# GPSPLLOCXO.net
KiCad netlist of a schematic drawn in EAGLE
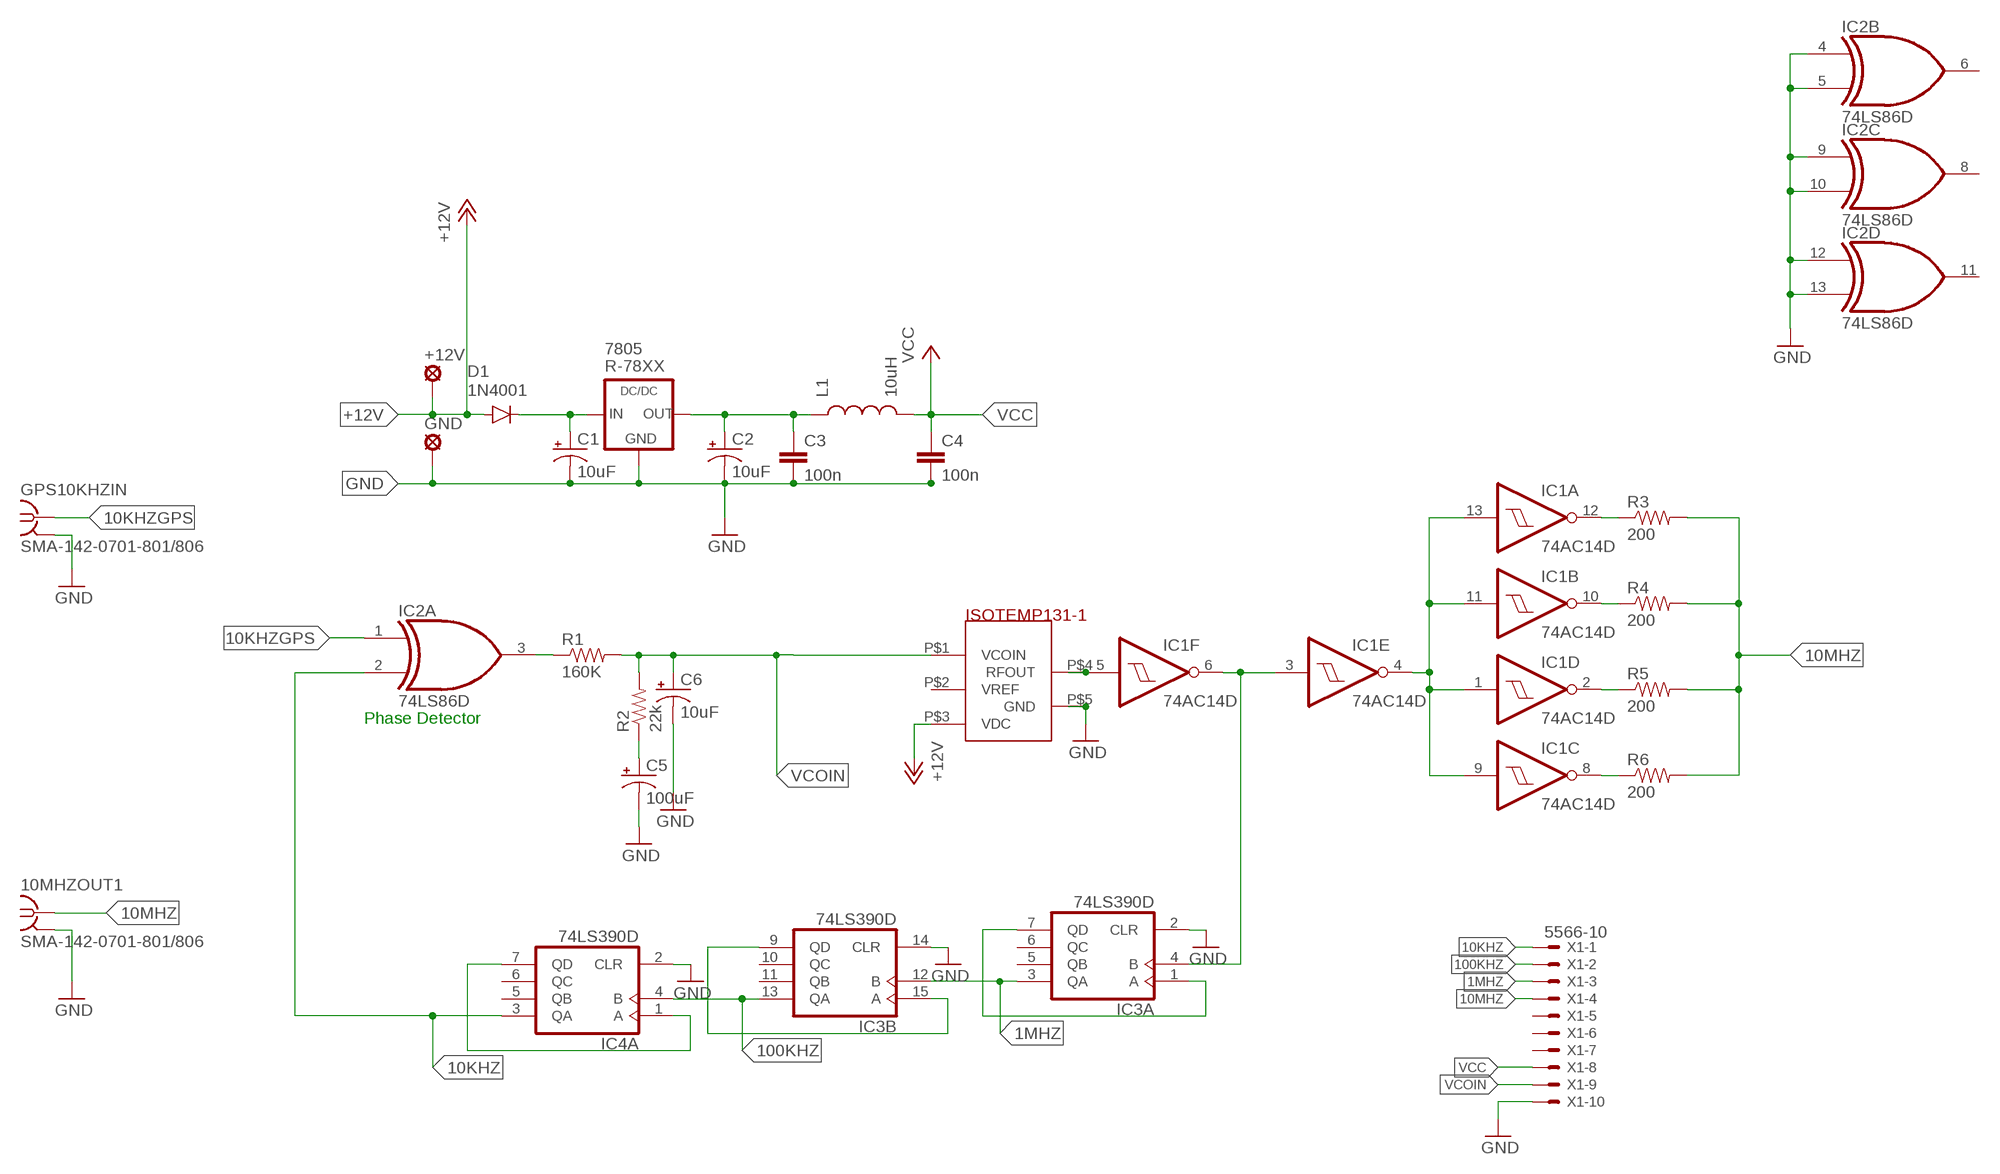
[diagram p0: schematic, sheet 1]

(export (version "E")
  (design (tool "Eeschema 10.0.6"))
  (components
    (comp (ref "+12V")
      (value "LSP13")
      (footprint "eagle-import:LSP13")
      (libsource (lib "eagle-import") (part "LSP13"))
    )
    (comp (ref "10MHZOUT1")
      (value "SMA-142-0701-801/806")
      (footprint "eagle-import:J502-ND-142-0701-801_806")
      (fields (field (name "MF") "JOHNSON COMPONENTS") (field (name "MPN") "142-0701-801"))
      (libsource (lib "eagle-import") (part "SMA-142-0701-801/806"))
    )
    (comp (ref "7805")
      (value "R-78XX")
      (footprint "eagle-import:R-78XX")
      (libsource (lib "eagle-import") (part "R-78XX"))
    )
    (comp (ref "C1")
      (value "10uF")
      (footprint "eagle-import:EIA3216")
      (libsource (lib "eagle-import") (part "10UF-16V-10%(TANT)"))
    )
    (comp (ref "C2")
      (value "10uF")
      (footprint "eagle-import:EIA3216")
      (libsource (lib "eagle-import") (part "10UF-16V-10%(TANT)"))
    )
    (comp (ref "C3")
      (value "100n")
      (footprint "eagle-import:0805")
      (libsource (lib "eagle-import") (part "1.0UF-25V-+80/-20(0805)"))
    )
    (comp (ref "C4")
      (value "100n")
      (footprint "eagle-import:0805")
      (libsource (lib "eagle-import") (part "1.0UF-25V-+80/-20(0805)"))
    )
    (comp (ref "C5")
      (value "100uF")
      (footprint "eagle-import:EIA7343")
      (libsource (lib "eagle-import") (part "100UF-10V-10%(TANT)"))
    )
    (comp (ref "C6")
      (value "10uF")
      (footprint "eagle-import:EIA3216")
      (libsource (lib "eagle-import") (part "10UF-16V-10%(TANT)"))
    )
    (comp (ref "D1")
      (value "1N4001")
      (footprint "eagle-import:SMA-DIODE")
      (libsource (lib "eagle-import") (part "DIODESMA"))
    )
    (comp (ref "GND")
      (value "LSP13")
      (footprint "eagle-import:LSP13")
      (libsource (lib "eagle-import") (part "LSP13"))
    )
    (comp (ref "GPS10KHZIN")
      (value "SMA-142-0701-801/806")
      (footprint "eagle-import:J502-ND-142-0701-801_806")
      (fields (field (name "MF") "JOHNSON COMPONENTS") (field (name "MPN") "142-0701-801"))
      (libsource (lib "eagle-import") (part "SMA-142-0701-801/806"))
    )
    (comp (ref "IC1")
      (value "74AC14D")
      (footprint "eagle-import:SO14")
      (libsource (lib "eagle-import") (part "7414DAC"))
    )
    (comp (ref "IC2")
      (value "74LS86D")
      (footprint "eagle-import:SO14")
      (libsource (lib "eagle-import") (part "7486DLS"))
    )
    (comp (ref "IC3")
      (value "74LS390D")
      (footprint "eagle-import:SO16")
      (libsource (lib "eagle-import") (part "74390DLS"))
    )
    (comp (ref "IC4")
      (value "74LS390D")
      (footprint "eagle-import:SO16")
      (libsource (lib "eagle-import") (part "74390DLS"))
    )
    (comp (ref "ISOTEMP131-1")
      (value "ISOTEMP-131-191")
      (footprint "eagle-import:131")
      (libsource (lib "eagle-import") (part "ISOTEMP-131-191"))
    )
    (comp (ref "L1")
      (value "10uH")
      (footprint "eagle-import:1210")
      (libsource (lib "eagle-import") (part "INDUCTOR1210"))
    )
    (comp (ref "R1")
      (value "160K")
      (footprint "eagle-import:0805")
      (libsource (lib "eagle-import") (part "RESISTOR0805-RES"))
    )
    (comp (ref "R2")
      (value "22k")
      (footprint "eagle-import:0805")
      (libsource (lib "eagle-import") (part "RESISTOR0805-RES"))
    )
    (comp (ref "R3")
      (value "200")
      (footprint "eagle-import:0805")
      (libsource (lib "eagle-import") (part "RESISTOR0805-RES"))
    )
    (comp (ref "R4")
      (value "200")
      (footprint "eagle-import:0805")
      (libsource (lib "eagle-import") (part "RESISTOR0805-RES"))
    )
    (comp (ref "R5")
      (value "200")
      (footprint "eagle-import:0805")
      (libsource (lib "eagle-import") (part "RESISTOR0805-RES"))
    )
    (comp (ref "R6")
      (value "200")
      (footprint "eagle-import:0805")
      (libsource (lib "eagle-import") (part "RESISTOR0805-RES"))
    )
    (comp (ref "X1")
      (value "5566-10")
      (footprint "eagle-import:5566-10")
      (libsource (lib "eagle-import") (part "5566-10"))
    )
  )
  (nets
    (net (code "1") (name "+12V") (class "Default")
      (node (ref "+12V") (pin "MP") (pinfunction "MP_MP") (pintype "passive"))
      (node (ref "D1") (pin "A") (pinfunction "A_A") (pintype "passive"))
      (node (ref "ISOTEMP131-1") (pin "P$3") (pinfunction "VDC_P$3") (pintype "power_in"))
    )
    (net (code "2") (name "1MHZ") (class "Default")
      (node (ref "IC3") (pin "12") (pinfunction "B_12") (pintype "input"))
      (node (ref "IC3") (pin "3") (pinfunction "QA_3") (pintype "output"))
      (node (ref "X1") (pin "3") (pinfunction "S_3") (pintype "passive"))
    )
    (net (code "3") (name "10KHZ") (class "Default")
      (node (ref "IC2") (pin "2") (pinfunction "I1_2") (pintype "input"))
      (node (ref "IC4") (pin "3") (pinfunction "QA_3") (pintype "output"))
      (node (ref "X1") (pin "1") (pinfunction "S_1") (pintype "passive"))
    )
    (net (code "4") (name "10KHZGPS") (class "Default")
      (node (ref "GPS10KHZIN") (pin "1") (pinfunction "1_1") (pintype "passive"))
      (node (ref "IC2") (pin "1") (pinfunction "I0_1") (pintype "input"))
    )
    (net (code "5") (name "10MHZ") (class "Default")
      (node (ref "10MHZOUT1") (pin "1") (pinfunction "1_1") (pintype "passive"))
      (node (ref "R3") (pin "2") (pinfunction "2_2") (pintype "passive"))
      (node (ref "R4") (pin "2") (pinfunction "2_2") (pintype "passive"))
      (node (ref "R5") (pin "2") (pinfunction "2_2") (pintype "passive"))
      (node (ref "R6") (pin "2") (pinfunction "2_2") (pintype "passive"))
      (node (ref "X1") (pin "4") (pinfunction "S_4") (pintype "passive"))
    )
    (net (code "6") (name "100KHZ") (class "Default")
      (node (ref "IC3") (pin "13") (pinfunction "QA_13") (pintype "output"))
      (node (ref "IC4") (pin "4") (pinfunction "B_4") (pintype "input"))
      (node (ref "X1") (pin "2") (pinfunction "S_2") (pintype "passive"))
    )
    (net (code "7") (name "GND") (class "Default")
      (node (ref "10MHZOUT1") (pin "G@1") (pinfunction "2_G@1") (pintype "passive"))
      (node (ref "10MHZOUT1") (pin "G@2") (pinfunction "2_G@2") (pintype "passive"))
      (node (ref "10MHZOUT1") (pin "G@3") (pinfunction "2_G@3") (pintype "passive"))
      (node (ref "10MHZOUT1") (pin "G@4") (pinfunction "2_G@4") (pintype "passive"))
      (node (ref "7805") (pin "2") (pinfunction "GND_2") (pintype "input"))
      (node (ref "C1") (pin "C") (pinfunction "-_C") (pintype "passive"))
      (node (ref "C2") (pin "C") (pinfunction "-_C") (pintype "passive"))
      (node (ref "C3") (pin "2") (pinfunction "2_2") (pintype "passive"))
      (node (ref "C4") (pin "2") (pinfunction "2_2") (pintype "passive"))
      (node (ref "C5") (pin "C") (pinfunction "-_C") (pintype "passive"))
      (node (ref "C6") (pin "C") (pinfunction "-_C") (pintype "passive"))
      (node (ref "GND") (pin "MP") (pinfunction "MP_MP") (pintype "passive"))
      (node (ref "GPS10KHZIN") (pin "G@1") (pinfunction "2_G@1") (pintype "passive"))
      (node (ref "GPS10KHZIN") (pin "G@2") (pinfunction "2_G@2") (pintype "passive"))
      (node (ref "GPS10KHZIN") (pin "G@3") (pinfunction "2_G@3") (pintype "passive"))
      (node (ref "GPS10KHZIN") (pin "G@4") (pinfunction "2_G@4") (pintype "passive"))
      (node (ref "IC2") (pin "10") (pinfunction "I1_10") (pintype "input"))
      (node (ref "IC2") (pin "12") (pinfunction "I0_12") (pintype "input"))
      (node (ref "IC2") (pin "13") (pinfunction "I1_13") (pintype "input"))
      (node (ref "IC2") (pin "4") (pinfunction "I0_4") (pintype "input"))
      (node (ref "IC2") (pin "5") (pinfunction "I1_5") (pintype "input"))
      (node (ref "IC2") (pin "9") (pinfunction "I0_9") (pintype "input"))
      (node (ref "IC3") (pin "14") (pinfunction "CLR_14") (pintype "input"))
      (node (ref "IC3") (pin "2") (pinfunction "CLR_2") (pintype "input"))
      (node (ref "IC4") (pin "2") (pinfunction "CLR_2") (pintype "input"))
      (node (ref "ISOTEMP131-1") (pin "P$5") (pinfunction "GND_P$5") (pintype "power_in"))
      (node (ref "X1") (pin "10") (pinfunction "S_10") (pintype "passive"))
    )
    (net (code "8") (name "Net-(7805-IN)") (class "Default")
      (node (ref "7805") (pin "1") (pinfunction "IN_1") (pintype "input"))
      (node (ref "C1") (pin "A") (pinfunction "+_A") (pintype "passive"))
      (node (ref "D1") (pin "C") (pinfunction "C_C") (pintype "passive"))
    )
    (net (code "9") (name "Net-(7805-OUT)") (class "Default")
      (node (ref "7805") (pin "3") (pinfunction "OUT_3") (pintype "passive"))
      (node (ref "C2") (pin "A") (pinfunction "+_A") (pintype "passive"))
      (node (ref "C3") (pin "1") (pinfunction "1_1") (pintype "passive"))
      (node (ref "L1") (pin "1") (pinfunction "1_1") (pintype "passive"))
    )
    (net (code "10") (name "Net-(C5-+)") (class "Default")
      (node (ref "C5") (pin "A") (pinfunction "+_A") (pintype "passive"))
      (node (ref "R2") (pin "1") (pinfunction "1_1") (pintype "passive"))
    )
    (net (code "11") (name "Net-(IC1A-I)") (class "Default")
      (node (ref "IC1") (pin "1") (pinfunction "I_1") (pintype "input"))
      (node (ref "IC1") (pin "11") (pinfunction "I_11") (pintype "input"))
      (node (ref "IC1") (pin "13") (pinfunction "I_13") (pintype "input"))
      (node (ref "IC1") (pin "4") (pinfunction "O_4") (pintype "output"))
      (node (ref "IC1") (pin "9") (pinfunction "I_9") (pintype "input"))
    )
    (net (code "12") (name "Net-(IC1A-O)") (class "Default")
      (node (ref "IC1") (pin "12") (pinfunction "O_12") (pintype "output"))
      (node (ref "R3") (pin "1") (pinfunction "1_1") (pintype "passive"))
    )
    (net (code "13") (name "Net-(IC1B-O)") (class "Default")
      (node (ref "IC1") (pin "10") (pinfunction "O_10") (pintype "output"))
      (node (ref "R4") (pin "1") (pinfunction "1_1") (pintype "passive"))
    )
    (net (code "14") (name "Net-(IC1C-O)") (class "Default")
      (node (ref "IC1") (pin "8") (pinfunction "O_8") (pintype "output"))
      (node (ref "R6") (pin "1") (pinfunction "1_1") (pintype "passive"))
    )
    (net (code "15") (name "Net-(IC1D-O)") (class "Default")
      (node (ref "IC1") (pin "2") (pinfunction "O_2") (pintype "output"))
      (node (ref "R5") (pin "1") (pinfunction "1_1") (pintype "passive"))
    )
    (net (code "16") (name "Net-(IC1E-I)") (class "Default")
      (node (ref "IC1") (pin "3") (pinfunction "I_3") (pintype "input"))
      (node (ref "IC1") (pin "6") (pinfunction "O_6") (pintype "output"))
      (node (ref "IC3") (pin "4") (pinfunction "B_4") (pintype "input"))
    )
    (net (code "17") (name "Net-(IC1F-I)") (class "Default")
      (node (ref "IC1") (pin "5") (pinfunction "I_5") (pintype "input"))
      (node (ref "ISOTEMP131-1") (pin "P$4") (pinfunction "RFOUT_P$4") (pintype "output"))
    )
    (net (code "18") (name "Net-(IC2A-O)") (class "Default")
      (node (ref "IC2") (pin "3") (pinfunction "O_3") (pintype "output"))
      (node (ref "R1") (pin "1") (pinfunction "1_1") (pintype "passive"))
    )
    (net (code "19") (name "Net-(IC3A-A)") (class "Default")
      (node (ref "IC3") (pin "1") (pinfunction "A_1") (pintype "input"))
      (node (ref "IC3") (pin "7") (pinfunction "QD_7") (pintype "output"))
    )
    (net (code "20") (name "Net-(IC3B-A)") (class "Default")
      (node (ref "IC3") (pin "15") (pinfunction "A_15") (pintype "input"))
      (node (ref "IC3") (pin "9") (pinfunction "QD_9") (pintype "output"))
    )
    (net (code "21") (name "Net-(IC4A-A)") (class "Default")
      (node (ref "IC4") (pin "1") (pinfunction "A_1") (pintype "input"))
      (node (ref "IC4") (pin "7") (pinfunction "QD_7") (pintype "output"))
    )
    (net (code "22") (name "VCC") (class "Default")
      (node (ref "C4") (pin "1") (pinfunction "1_1") (pintype "passive"))
      (node (ref "L1") (pin "2") (pinfunction "2_2") (pintype "passive"))
      (node (ref "X1") (pin "8") (pinfunction "S_8") (pintype "passive"))
    )
    (net (code "23") (name "VCOIN") (class "Default")
      (node (ref "C6") (pin "A") (pinfunction "+_A") (pintype "passive"))
      (node (ref "ISOTEMP131-1") (pin "P$1") (pinfunction "VCOIN_P$1") (pintype "input"))
      (node (ref "R1") (pin "2") (pinfunction "2_2") (pintype "passive"))
      (node (ref "R2") (pin "2") (pinfunction "2_2") (pintype "passive"))
      (node (ref "X1") (pin "9") (pinfunction "S_9") (pintype "passive"))
    )
    (net (code "24") (name "unconnected-(IC2B-O-Pad6)") (class "Default")
      (node (ref "IC2") (pin "6") (pinfunction "O_6") (pintype "output"))
    )
    (net (code "25") (name "unconnected-(IC2C-O-Pad8)") (class "Default")
      (node (ref "IC2") (pin "8") (pinfunction "O_8") (pintype "output"))
    )
    (net (code "26") (name "unconnected-(IC2D-O-Pad11)") (class "Default")
      (node (ref "IC2") (pin "11") (pinfunction "O_11") (pintype "output"))
    )
    (net (code "27") (name "unconnected-(IC3A-QB-Pad5)") (class "Default")
      (node (ref "IC3") (pin "5") (pinfunction "QB_5") (pintype "output"))
    )
    (net (code "28") (name "unconnected-(IC3A-QC-Pad6)") (class "Default")
      (node (ref "IC3") (pin "6") (pinfunction "QC_6") (pintype "output"))
    )
    (net (code "29") (name "unconnected-(IC3B-QB-Pad11)") (class "Default")
      (node (ref "IC3") (pin "11") (pinfunction "QB_11") (pintype "output"))
    )
    (net (code "30") (name "unconnected-(IC3B-QC-Pad10)") (class "Default")
      (node (ref "IC3") (pin "10") (pinfunction "QC_10") (pintype "output"))
    )
    (net (code "31") (name "unconnected-(IC4A-QB-Pad5)") (class "Default")
      (node (ref "IC4") (pin "5") (pinfunction "QB_5") (pintype "output"))
    )
    (net (code "32") (name "unconnected-(IC4A-QC-Pad6)") (class "Default")
      (node (ref "IC4") (pin "6") (pinfunction "QC_6") (pintype "output"))
    )
    (net (code "33") (name "unconnected-(ISOTEMP131-1-VREF-PadP$2)") (class "Default")
      (node (ref "ISOTEMP131-1") (pin "P$2") (pinfunction "VREF_P$2") (pintype "output"))
    )
    (net (code "34") (name "unconnected-(X1F-S-Pad5)") (class "Default")
      (node (ref "X1") (pin "5") (pinfunction "S_5") (pintype "passive"))
    )
    (net (code "35") (name "unconnected-(X1G-S-Pad6)") (class "Default")
      (node (ref "X1") (pin "6") (pinfunction "S_6") (pintype "passive"))
    )
    (net (code "36") (name "unconnected-(X1H-S-Pad7)") (class "Default")
      (node (ref "X1") (pin "7") (pinfunction "S_7") (pintype "passive"))
    )
  )
)
